# motor_driver.net
KiCad netlist of a schematic drawn in EAGLE
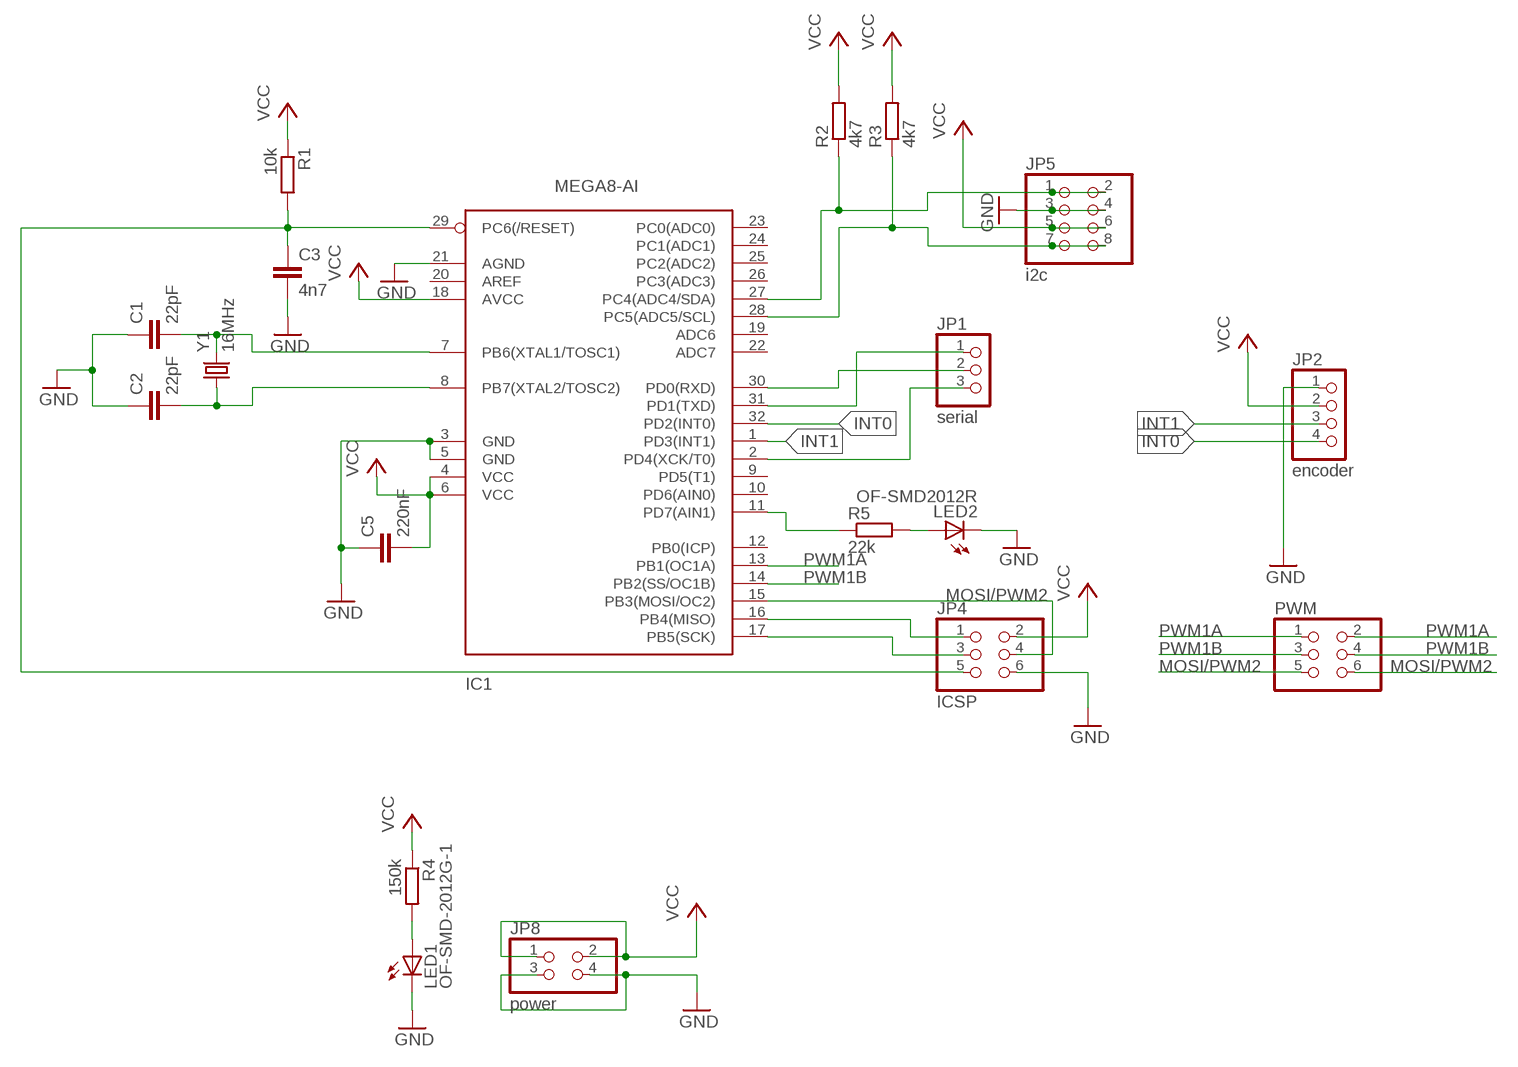
[diagram p0: schematic, sheet 1]

(export (version "E")
  (design (tool "Eeschema 10.0.6"))
  (components
    (comp (ref "C1")
      (value "22pF")
      (footprint "eagle-import:1206")
      (libsource (lib "eagle-import") (part "CAP1206"))
    )
    (comp (ref "C2")
      (value "22pF")
      (footprint "eagle-import:1206")
      (libsource (lib "eagle-import") (part "CAP1206"))
    )
    (comp (ref "C3")
      (value "4n7")
      (footprint "eagle-import:1206")
      (libsource (lib "eagle-import") (part "CAP1206"))
    )
    (comp (ref "C5")
      (value "220nF")
      (footprint "eagle-import:0805")
      (libsource (lib "eagle-import") (part "CAP0805"))
    )
    (comp (ref "IC1")
      (value "MEGA8-AI")
      (footprint "eagle-import:TQFP32-08")
      (libsource (lib "eagle-import") (part "MEGA8-AI"))
    )
    (comp (ref "JP1")
      (value "serial")
      (footprint "eagle-import:1X03-S")
      (libsource (lib "eagle-import") (part "PINHD-1X03_2.54-S"))
    )
    (comp (ref "JP2")
      (value "encoder")
      (footprint "eagle-import:1X04-S")
      (libsource (lib "eagle-import") (part "PINHD-1X04_2.54-S"))
    )
    (comp (ref "JP4")
      (value "ICSP")
      (footprint "eagle-import:2X03")
      (libsource (lib "eagle-import") (part "PINHD-2X03_2.54"))
    )
    (comp (ref "JP5")
      (value "i2c")
      (footprint "eagle-import:2X04")
      (libsource (lib "eagle-import") (part "PINHD-2X04_2.54"))
    )
    (comp (ref "JP8")
      (value "power")
      (footprint "eagle-import:2X02")
      (libsource (lib "eagle-import") (part "PINHD-2X02_2.54"))
    )
    (comp (ref "LED1")
      (value "OF-SMD-2012G-1")
      (footprint "eagle-import:LED3MM")
      (libsource (lib "eagle-import") (part "LED3MM"))
    )
    (comp (ref "LED2")
      (value "OF-SMD2012R")
      (footprint "eagle-import:LED3MM")
      (libsource (lib "eagle-import") (part "LED3MM"))
    )
    (comp (ref "PWM")
      (value "PINHD-2X3")
      (footprint "eagle-import:2X03")
      (libsource (lib "eagle-import") (part "PINHD-2X3"))
    )
    (comp (ref "R1")
      (value "10k")
      (footprint "eagle-import:R1206")
      (libsource (lib "eagle-import") (part "RR1206"))
    )
    (comp (ref "R2")
      (value "4k7")
      (footprint "eagle-import:R1206")
      (libsource (lib "eagle-import") (part "RR1206"))
    )
    (comp (ref "R3")
      (value "4k7")
      (footprint "eagle-import:R1206")
      (libsource (lib "eagle-import") (part "RR1206"))
    )
    (comp (ref "R4")
      (value "150k")
      (footprint "eagle-import:R0805")
      (libsource (lib "eagle-import") (part "R"))
    )
    (comp (ref "R5")
      (value "22k")
      (footprint "eagle-import:R0805")
      (libsource (lib "eagle-import") (part "R"))
    )
    (comp (ref "Y1")
      (value "16MHz")
      (footprint "eagle-import:HC49UP")
      (libsource (lib "eagle-import") (part "CRYSTALSMD"))
    )
  )
  (nets
    (net (code "1") (name "/MOSI{slash}PWM2") (class "Default")
      (node (ref "IC1") (pin "15") (pinfunction "PB3(MOSI/OC2)_15") (pintype "bidirectional"))
      (node (ref "JP4") (pin "4") (pinfunction "4_4") (pintype "passive"))
      (node (ref "PWM") (pin "5") (pinfunction "5_5") (pintype "passive"))
      (node (ref "PWM") (pin "6") (pinfunction "6_6") (pintype "passive"))
    )
    (net (code "2") (name "/PWM1A") (class "Default")
      (node (ref "IC1") (pin "13") (pinfunction "PB1(OC1A)_13") (pintype "bidirectional"))
      (node (ref "PWM") (pin "1") (pinfunction "1_1") (pintype "passive"))
      (node (ref "PWM") (pin "2") (pinfunction "2_2") (pintype "passive"))
    )
    (net (code "3") (name "/PWM1B") (class "Default")
      (node (ref "IC1") (pin "14") (pinfunction "PB2(SS/OC1B)_14") (pintype "bidirectional"))
      (node (ref "PWM") (pin "3") (pinfunction "3_3") (pintype "passive"))
      (node (ref "PWM") (pin "4") (pinfunction "4_4") (pintype "passive"))
    )
    (net (code "4") (name "GND") (class "Default")
      (node (ref "C1") (pin "1") (pinfunction "1_1") (pintype "passive"))
      (node (ref "C2") (pin "1") (pinfunction "1_1") (pintype "passive"))
      (node (ref "C3") (pin "2") (pinfunction "2_2") (pintype "passive"))
      (node (ref "C5") (pin "1") (pinfunction "1_1") (pintype "passive"))
      (node (ref "IC1") (pin "21") (pinfunction "AGND_21") (pintype "bidirectional"))
      (node (ref "IC1") (pin "3") (pinfunction "GND_3") (pintype "bidirectional"))
      (node (ref "IC1") (pin "5") (pinfunction "GND_5") (pintype "bidirectional"))
      (node (ref "JP2") (pin "1") (pinfunction "1_1") (pintype "passive"))
      (node (ref "JP4") (pin "6") (pinfunction "6_6") (pintype "passive"))
      (node (ref "JP5") (pin "3") (pinfunction "3_3") (pintype "passive"))
      (node (ref "JP5") (pin "4") (pinfunction "4_4") (pintype "passive"))
      (node (ref "JP8") (pin "3") (pinfunction "3_3") (pintype "passive"))
      (node (ref "JP8") (pin "4") (pinfunction "4_4") (pintype "passive"))
      (node (ref "LED1") (pin "K") (pinfunction "C_K") (pintype "passive"))
      (node (ref "LED2") (pin "K") (pinfunction "C_K") (pintype "passive"))
    )
    (net (code "5") (name "INT0") (class "Default")
      (node (ref "IC1") (pin "32") (pinfunction "PD2(INT0)_32") (pintype "bidirectional"))
      (node (ref "JP2") (pin "4") (pinfunction "4_4") (pintype "passive"))
    )
    (net (code "6") (name "INT1") (class "Default")
      (node (ref "IC1") (pin "1") (pinfunction "PD3(INT1)_1") (pintype "bidirectional"))
      (node (ref "JP2") (pin "3") (pinfunction "3_3") (pintype "passive"))
    )
    (net (code "7") (name "Net-(IC1-PB4(MISO))") (class "Default")
      (node (ref "IC1") (pin "16") (pinfunction "PB4(MISO)_16") (pintype "bidirectional"))
      (node (ref "JP4") (pin "1") (pinfunction "1_1") (pintype "passive"))
    )
    (net (code "8") (name "Net-(IC1-PB5(SCK))") (class "Default")
      (node (ref "IC1") (pin "17") (pinfunction "PB5(SCK)_17") (pintype "bidirectional"))
      (node (ref "JP4") (pin "3") (pinfunction "3_3") (pintype "passive"))
    )
    (net (code "9") (name "Net-(IC1-PB6(XTAL1{slash}TOSC1))") (class "Default")
      (node (ref "C1") (pin "2") (pinfunction "2_2") (pintype "passive"))
      (node (ref "IC1") (pin "7") (pinfunction "PB6(XTAL1/TOSC1)_7") (pintype "bidirectional"))
      (node (ref "Y1") (pin "2") (pinfunction "2_2") (pintype "passive"))
    )
    (net (code "10") (name "Net-(IC1-PB7(XTAL2{slash}TOSC2))") (class "Default")
      (node (ref "C2") (pin "2") (pinfunction "2_2") (pintype "passive"))
      (node (ref "IC1") (pin "8") (pinfunction "PB7(XTAL2/TOSC2)_8") (pintype "bidirectional"))
      (node (ref "Y1") (pin "1") (pinfunction "1_1") (pintype "passive"))
    )
    (net (code "11") (name "Net-(IC1-PC4(ADC4{slash}SDA))") (class "Default")
      (node (ref "IC1") (pin "27") (pinfunction "PC4(ADC4/SDA)_27") (pintype "bidirectional"))
      (node (ref "JP5") (pin "1") (pinfunction "1_1") (pintype "passive"))
      (node (ref "JP5") (pin "2") (pinfunction "2_2") (pintype "passive"))
      (node (ref "R2") (pin "1") (pinfunction "1_1") (pintype "passive"))
    )
    (net (code "12") (name "Net-(IC1-PC5(ADC5{slash}SCL))") (class "Default")
      (node (ref "IC1") (pin "28") (pinfunction "PC5(ADC5/SCL)_28") (pintype "bidirectional"))
      (node (ref "JP5") (pin "7") (pinfunction "7_7") (pintype "passive"))
      (node (ref "JP5") (pin "8") (pinfunction "8_8") (pintype "passive"))
      (node (ref "R3") (pin "1") (pinfunction "1_1") (pintype "passive"))
    )
    (net (code "13") (name "Net-(IC1-PC6({slash}RESET))") (class "Default")
      (node (ref "C3") (pin "1") (pinfunction "1_1") (pintype "passive"))
      (node (ref "IC1") (pin "29") (pinfunction "PC6(/RESET)_29") (pintype "bidirectional"))
      (node (ref "JP4") (pin "5") (pinfunction "5_5") (pintype "passive"))
      (node (ref "R1") (pin "2") (pinfunction "2_2") (pintype "passive"))
    )
    (net (code "14") (name "Net-(IC1-PD0(RXD))") (class "Default")
      (node (ref "IC1") (pin "30") (pinfunction "PD0(RXD)_30") (pintype "bidirectional"))
      (node (ref "JP1") (pin "2") (pinfunction "2_2") (pintype "passive"))
    )
    (net (code "15") (name "Net-(IC1-PD1(TXD))") (class "Default")
      (node (ref "IC1") (pin "31") (pinfunction "PD1(TXD)_31") (pintype "bidirectional"))
      (node (ref "JP1") (pin "1") (pinfunction "1_1") (pintype "passive"))
    )
    (net (code "16") (name "Net-(IC1-PD4(XCK{slash}T0))") (class "Default")
      (node (ref "IC1") (pin "2") (pinfunction "PD4(XCK/T0)_2") (pintype "bidirectional"))
      (node (ref "JP1") (pin "3") (pinfunction "3_3") (pintype "passive"))
    )
    (net (code "17") (name "Net-(IC1-PD7(AIN1))") (class "Default")
      (node (ref "IC1") (pin "11") (pinfunction "PD7(AIN1)_11") (pintype "bidirectional"))
      (node (ref "R5") (pin "1") (pinfunction "1_1") (pintype "passive"))
    )
    (net (code "18") (name "Net-(LED1-PadA)") (class "Default")
      (node (ref "LED1") (pin "A") (pinfunction "A_A") (pintype "passive"))
      (node (ref "R4") (pin "2") (pinfunction "2_2") (pintype "passive"))
    )
    (net (code "19") (name "Net-(LED2-PadA)") (class "Default")
      (node (ref "LED2") (pin "A") (pinfunction "A_A") (pintype "passive"))
      (node (ref "R5") (pin "2") (pinfunction "2_2") (pintype "passive"))
    )
    (net (code "20") (name "VCC") (class "Default")
      (node (ref "C5") (pin "2") (pinfunction "2_2") (pintype "passive"))
      (node (ref "IC1") (pin "18") (pinfunction "AVCC_18") (pintype "bidirectional"))
      (node (ref "IC1") (pin "4") (pinfunction "VCC_4") (pintype "bidirectional"))
      (node (ref "IC1") (pin "6") (pinfunction "VCC_6") (pintype "bidirectional"))
      (node (ref "JP2") (pin "2") (pinfunction "2_2") (pintype "passive"))
      (node (ref "JP4") (pin "2") (pinfunction "2_2") (pintype "passive"))
      (node (ref "JP5") (pin "5") (pinfunction "5_5") (pintype "passive"))
      (node (ref "JP5") (pin "6") (pinfunction "6_6") (pintype "passive"))
      (node (ref "JP8") (pin "1") (pinfunction "1_1") (pintype "passive"))
      (node (ref "JP8") (pin "2") (pinfunction "2_2") (pintype "passive"))
      (node (ref "R1") (pin "1") (pinfunction "1_1") (pintype "passive"))
      (node (ref "R2") (pin "2") (pinfunction "2_2") (pintype "passive"))
      (node (ref "R3") (pin "2") (pinfunction "2_2") (pintype "passive"))
      (node (ref "R4") (pin "1") (pinfunction "1_1") (pintype "passive"))
    )
    (net (code "21") (name "unconnected-(IC1-ADC6-Pad19)") (class "Default")
      (node (ref "IC1") (pin "19") (pinfunction "ADC6_19") (pintype "bidirectional"))
    )
    (net (code "22") (name "unconnected-(IC1-ADC7-Pad22)") (class "Default")
      (node (ref "IC1") (pin "22") (pinfunction "ADC7_22") (pintype "bidirectional"))
    )
    (net (code "23") (name "unconnected-(IC1-AREF-Pad20)") (class "Default")
      (node (ref "IC1") (pin "20") (pinfunction "AREF_20") (pintype "bidirectional"))
    )
    (net (code "24") (name "unconnected-(IC1-PB0(ICP)-Pad12)") (class "Default")
      (node (ref "IC1") (pin "12") (pinfunction "PB0(ICP)_12") (pintype "bidirectional"))
    )
    (net (code "25") (name "unconnected-(IC1-PC0(ADC0)-Pad23)") (class "Default")
      (node (ref "IC1") (pin "23") (pinfunction "PC0(ADC0)_23") (pintype "bidirectional"))
    )
    (net (code "26") (name "unconnected-(IC1-PC1(ADC1)-Pad24)") (class "Default")
      (node (ref "IC1") (pin "24") (pinfunction "PC1(ADC1)_24") (pintype "bidirectional"))
    )
    (net (code "27") (name "unconnected-(IC1-PC2(ADC2)-Pad25)") (class "Default")
      (node (ref "IC1") (pin "25") (pinfunction "PC2(ADC2)_25") (pintype "bidirectional"))
    )
    (net (code "28") (name "unconnected-(IC1-PC3(ADC3)-Pad26)") (class "Default")
      (node (ref "IC1") (pin "26") (pinfunction "PC3(ADC3)_26") (pintype "bidirectional"))
    )
    (net (code "29") (name "unconnected-(IC1-PD5(T1)-Pad9)") (class "Default")
      (node (ref "IC1") (pin "9") (pinfunction "PD5(T1)_9") (pintype "bidirectional"))
    )
    (net (code "30") (name "unconnected-(IC1-PD6(AIN0)-Pad10)") (class "Default")
      (node (ref "IC1") (pin "10") (pinfunction "PD6(AIN0)_10") (pintype "bidirectional"))
    )
  )
)
